# versterker_L.net
KiCad netlist of a schematic drawn in Altium Designer
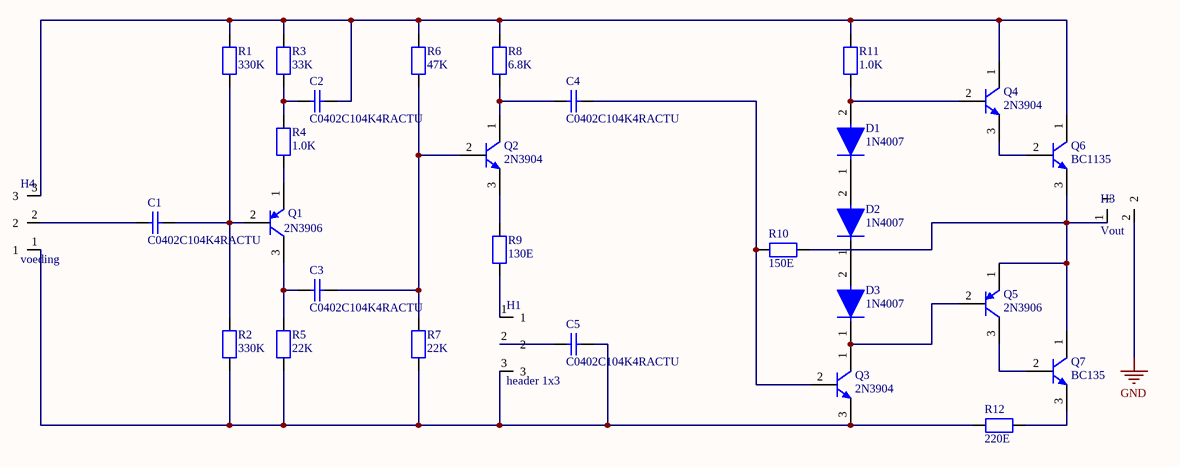
[diagram p0: versterker_L.SchDoc]

(export (version "E")
  (design (tool "Eeschema 10.0.6"))
  (components
    (comp (ref "C1")
      (value "C0402C104K4RACTU")
      (footprint "capacitor SMD")
      (fields (field (name "MANUFACTURER") "Kemet"))
      (libsource (lib "basisSchematicLibrary") (part "capacitor smd"))
    )
    (comp (ref "C2")
      (value "C0402C104K4RACTU")
      (footprint "capacitor SMD")
      (fields (field (name "MANUFACTURER") "Kemet"))
      (libsource (lib "basisSchematicLibrary") (part "capacitor smd"))
    )
    (comp (ref "C3")
      (value "C0402C104K4RACTU")
      (footprint "capacitor SMD")
      (fields (field (name "MANUFACTURER") "Kemet"))
      (libsource (lib "basisSchematicLibrary") (part "capacitor smd"))
    )
    (comp (ref "C4")
      (value "C0402C104K4RACTU")
      (footprint "capacitor SMD")
      (fields (field (name "MANUFACTURER") "Kemet"))
      (libsource (lib "basisSchematicLibrary") (part "capacitor smd"))
    )
    (comp (ref "C5")
      (value "C0402C104K4RACTU")
      (footprint "capacitor SMD")
      (fields (field (name "MANUFACTURER") "Kemet"))
      (libsource (lib "basisSchematicLibrary") (part "capacitor smd"))
    )
    (comp (ref "D1")
      (value "1N4007")
      (footprint "diode")
      (description "Rectifier diode 1000 V 1 A DO-41, ,")
      (fields
        (field (name "MANUFACTURER") "Diotec")
        (field (name "OCTOPART") "https://octopart.com/1n4007-diotec-4040411")
      )
      (libsource (lib "basisSchematicLibrary") (part "diode"))
    )
    (comp (ref "D2")
      (value "1N4007")
      (footprint "diode")
      (description "Rectifier diode 1000 V 1 A DO-41, ,")
      (fields
        (field (name "MANUFACTURER") "Diotec")
        (field (name "OCTOPART") "https://octopart.com/1n4007-diotec-4040411")
      )
      (libsource (lib "basisSchematicLibrary") (part "diode"))
    )
    (comp (ref "D3")
      (value "1N4007")
      (footprint "diode")
      (description "Rectifier diode 1000 V 1 A DO-41, ,")
      (fields
        (field (name "MANUFACTURER") "Diotec")
        (field (name "OCTOPART") "https://octopart.com/1n4007-diotec-4040411")
      )
      (libsource (lib "basisSchematicLibrary") (part "diode"))
    )
    (comp (ref "H1")
      (value "header 1x3")
      (footprint "header 1x3")
      (libsource (lib "headerSchematicLibrary") (part "header 1x3"))
    )
    (comp (ref "H3")
      (value "Vout")
      (footprint "header 1x2")
      (libsource (lib "headerSchematicLibrary") (part "header 1x2"))
    )
    (comp (ref "H4")
      (value "voeding")
      (footprint "header 1x3")
      (libsource (lib "headerSchematicLibrary") (part "header 1x3"))
    )
    (comp (ref "Q1")
      (value "2N3906")
      (footprint "transistor")
      (description "Amplifier Transistor, NPN Silicon, 3-Pin TO-92, Bulk Box")
      (fields (field (name "MANUFACTURER") "On Semiconductor") (field (name "PARTNUMBER") "BC547B"))
      (libsource (lib "basisSchematicLibrary") (part "pnp transistor"))
    )
    (comp (ref "Q2")
      (value "2N3904")
      (footprint "transistor")
      (description "Amplifier Transistor, NPN Silicon, 3-Pin TO-92, Bulk Box")
      (fields (field (name "MANUFACTURER") "On Semiconductor") (field (name "PARTNUMBER") "BC547B"))
      (libsource (lib "basisSchematicLibrary") (part "npn transistor"))
    )
    (comp (ref "Q3")
      (value "2N3904")
      (footprint "transistor")
      (description "Amplifier Transistor, NPN Silicon, 3-Pin TO-92, Bulk Box")
      (fields (field (name "MANUFACTURER") "On Semiconductor") (field (name "PARTNUMBER") "BC547B"))
      (libsource (lib "basisSchematicLibrary") (part "npn transistor"))
    )
    (comp (ref "Q4")
      (value "2N3904")
      (footprint "transistor")
      (description "Amplifier Transistor, NPN Silicon, 3-Pin TO-92, Bulk Box")
      (fields (field (name "MANUFACTURER") "On Semiconductor") (field (name "PARTNUMBER") "BC547B"))
      (libsource (lib "basisSchematicLibrary") (part "npn transistor"))
    )
    (comp (ref "Q5")
      (value "2N3906")
      (footprint "transistor")
      (description "Amplifier Transistor, NPN Silicon, 3-Pin TO-92, Bulk Box")
      (fields (field (name "MANUFACTURER") "On Semiconductor") (field (name "PARTNUMBER") "BC547B"))
      (libsource (lib "basisSchematicLibrary") (part "pnp transistor"))
    )
    (comp (ref "Q6")
      (value "BC1135")
      (footprint "transistor")
      (description "Amplifier Transistor, NPN Silicon, 3-Pin TO-92, Bulk Box")
      (fields (field (name "MANUFACTURER") "On Semiconductor") (field (name "PARTNUMBER") "BC547B"))
      (libsource (lib "basisSchematicLibrary") (part "npn transistor"))
    )
    (comp (ref "Q7")
      (value "BC135")
      (footprint "transistor")
      (description "Amplifier Transistor, NPN Silicon, 3-Pin TO-92, Bulk Box")
      (fields (field (name "MANUFACTURER") "On Semiconductor") (field (name "PARTNUMBER") "BC547B"))
      (libsource (lib "basisSchematicLibrary") (part "npn transistor"))
    )
    (comp (ref "R1")
      (value "330K")
      (footprint "resistor smd")
      (fields (field (name "MANUFACTURER") "Vishay Dale") (field (name "PART NUMBER") "CRCW08050000Z0EA"))
      (libsource (lib "basisSchematicLibrary") (part "resistor smd"))
    )
    (comp (ref "R2")
      (value "330K")
      (footprint "resistor smd")
      (fields (field (name "MANUFACTURER") "Vishay Dale") (field (name "PART NUMBER") "CRCW08050000Z0EA"))
      (libsource (lib "basisSchematicLibrary") (part "resistor smd"))
    )
    (comp (ref "R3")
      (value "33K")
      (footprint "resistor smd")
      (fields (field (name "MANUFACTURER") "Vishay Dale") (field (name "PART NUMBER") "CRCW08050000Z0EA"))
      (libsource (lib "basisSchematicLibrary") (part "resistor smd"))
    )
    (comp (ref "R4")
      (value "1.0K")
      (footprint "resistor smd")
      (fields (field (name "MANUFACTURER") "Vishay Dale") (field (name "PART NUMBER") "CRCW08050000Z0EA"))
      (libsource (lib "basisSchematicLibrary") (part "resistor smd"))
    )
    (comp (ref "R5")
      (value "22K")
      (footprint "resistor smd")
      (fields (field (name "MANUFACTURER") "Vishay Dale") (field (name "PART NUMBER") "CRCW08050000Z0EA"))
      (libsource (lib "basisSchematicLibrary") (part "resistor smd"))
    )
    (comp (ref "R6")
      (value "47K")
      (footprint "resistor smd")
      (fields (field (name "MANUFACTURER") "Vishay Dale") (field (name "PART NUMBER") "CRCW08050000Z0EA"))
      (libsource (lib "basisSchematicLibrary") (part "resistor smd"))
    )
    (comp (ref "R7")
      (value "22K")
      (footprint "resistor smd")
      (fields (field (name "MANUFACTURER") "Vishay Dale") (field (name "PART NUMBER") "CRCW08050000Z0EA"))
      (libsource (lib "basisSchematicLibrary") (part "resistor smd"))
    )
    (comp (ref "R8")
      (value "6.8K")
      (footprint "resistor smd")
      (fields (field (name "MANUFACTURER") "Vishay Dale") (field (name "PART NUMBER") "CRCW08050000Z0EA"))
      (libsource (lib "basisSchematicLibrary") (part "resistor smd"))
    )
    (comp (ref "R9")
      (value "130E")
      (footprint "resistor smd")
      (fields (field (name "MANUFACTURER") "Vishay Dale") (field (name "PART NUMBER") "CRCW08050000Z0EA"))
      (libsource (lib "basisSchematicLibrary") (part "resistor smd"))
    )
    (comp (ref "R10")
      (value "150E")
      (footprint "resistor smd")
      (fields (field (name "MANUFACTURER") "Vishay Dale") (field (name "PART NUMBER") "CRCW08050000Z0EA"))
      (libsource (lib "basisSchematicLibrary") (part "resistor smd"))
    )
    (comp (ref "R11")
      (value "1.0K")
      (footprint "resistor smd")
      (fields (field (name "MANUFACTURER") "Vishay Dale") (field (name "PART NUMBER") "CRCW08050000Z0EA"))
      (libsource (lib "basisSchematicLibrary") (part "resistor smd"))
    )
    (comp (ref "R12")
      (value "220E")
      (footprint "resistor smd")
      (fields (field (name "MANUFACTURER") "Vishay Dale") (field (name "PART NUMBER") "CRCW08050000Z0EA"))
      (libsource (lib "basisSchematicLibrary") (part "resistor smd"))
    )
  )
  (nets
    (net (code "1") (name "GND") (class "Default")
      (node (ref "H3") (pin "2") (pinfunction "2_2") (pintype "passive"))
    )
    (net (code "2") (name "Net-(C1-Pad1)") (class "Default")
      (node (ref "C1") (pin "1") (pinfunction "1_1") (pintype "passive"))
      (node (ref "H4") (pin "2") (pinfunction "2_2") (pintype "passive"))
    )
    (net (code "3") (name "Net-(C2-Pad1)") (class "Default")
      (node (ref "C2") (pin "1") (pinfunction "1_1") (pintype "passive"))
      (node (ref "R3") (pin "1") (pinfunction "1_1") (pintype "passive"))
      (node (ref "R4") (pin "2") (pinfunction "2_2") (pintype "passive"))
    )
    (net (code "4") (name "Net-(C5-Pad1)") (class "Default")
      (node (ref "C5") (pin "1") (pinfunction "1_1") (pintype "passive"))
      (node (ref "H1") (pin "2") (pinfunction "2_2") (pintype "passive"))
    )
    (net (code "5") (name "Net-(D1-A)") (class "Default")
      (node (ref "D1") (pin "2") (pinfunction "A_2") (pintype "passive"))
      (node (ref "Q4") (pin "2") (pinfunction "B_2") (pintype "passive"))
      (node (ref "R11") (pin "1") (pinfunction "1_1") (pintype "passive"))
    )
    (net (code "6") (name "Net-(D1-C)") (class "Default")
      (node (ref "D1") (pin "1") (pinfunction "C_1") (pintype "passive"))
      (node (ref "D2") (pin "2") (pinfunction "A_2") (pintype "passive"))
    )
    (net (code "7") (name "Net-(D2-C)") (class "Default")
      (node (ref "D2") (pin "1") (pinfunction "C_1") (pintype "passive"))
      (node (ref "D3") (pin "2") (pinfunction "A_2") (pintype "passive"))
    )
    (net (code "8") (name "Net-(D3-C)") (class "Default")
      (node (ref "D3") (pin "1") (pinfunction "C_1") (pintype "passive"))
      (node (ref "Q3") (pin "1") (pinfunction "C_1") (pintype "passive"))
      (node (ref "Q5") (pin "2") (pinfunction "B_2") (pintype "passive"))
    )
    (net (code "9") (name "Net-(H1-Pad1)") (class "Default")
      (node (ref "H1") (pin "1") (pinfunction "1_1") (pintype "passive"))
      (node (ref "R9") (pin "1") (pinfunction "1_1") (pintype "passive"))
    )
    (net (code "10") (name "Net-(Q1-B)") (class "Default")
      (node (ref "C1") (pin "2") (pinfunction "2_2") (pintype "passive"))
      (node (ref "Q1") (pin "2") (pinfunction "B_2") (pintype "passive"))
      (node (ref "R1") (pin "1") (pinfunction "1_1") (pintype "passive"))
      (node (ref "R2") (pin "2") (pinfunction "2_2") (pintype "passive"))
    )
    (net (code "11") (name "Net-(Q1-C)") (class "Default")
      (node (ref "Q1") (pin "1") (pinfunction "C_1") (pintype "passive"))
      (node (ref "R4") (pin "1") (pinfunction "1_1") (pintype "passive"))
    )
    (net (code "12") (name "Net-(Q1-E)") (class "Default")
      (node (ref "C3") (pin "1") (pinfunction "1_1") (pintype "passive"))
      (node (ref "Q1") (pin "3") (pinfunction "E_3") (pintype "passive"))
      (node (ref "R5") (pin "2") (pinfunction "2_2") (pintype "passive"))
    )
    (net (code "13") (name "Net-(Q2-B)") (class "Default")
      (node (ref "C3") (pin "2") (pinfunction "2_2") (pintype "passive"))
      (node (ref "Q2") (pin "2") (pinfunction "B_2") (pintype "passive"))
      (node (ref "R6") (pin "1") (pinfunction "1_1") (pintype "passive"))
      (node (ref "R7") (pin "2") (pinfunction "2_2") (pintype "passive"))
    )
    (net (code "14") (name "Net-(Q2-C)") (class "Default")
      (node (ref "C4") (pin "1") (pinfunction "1_1") (pintype "passive"))
      (node (ref "Q2") (pin "1") (pinfunction "C_1") (pintype "passive"))
      (node (ref "R8") (pin "1") (pinfunction "1_1") (pintype "passive"))
    )
    (net (code "15") (name "Net-(Q2-E)") (class "Default")
      (node (ref "Q2") (pin "3") (pinfunction "E_3") (pintype "passive"))
      (node (ref "R9") (pin "2") (pinfunction "2_2") (pintype "passive"))
    )
    (net (code "16") (name "Net-(Q3-B)") (class "Default")
      (node (ref "C4") (pin "2") (pinfunction "2_2") (pintype "passive"))
      (node (ref "Q3") (pin "2") (pinfunction "B_2") (pintype "passive"))
      (node (ref "R10") (pin "1") (pinfunction "1_1") (pintype "passive"))
    )
    (net (code "17") (name "Net-(Q3-E)") (class "Default")
      (node (ref "C5") (pin "2") (pinfunction "2_2") (pintype "passive"))
      (node (ref "H1") (pin "3") (pinfunction "3_3") (pintype "passive"))
      (node (ref "H4") (pin "1") (pinfunction "1_1") (pintype "passive"))
      (node (ref "Q3") (pin "3") (pinfunction "E_3") (pintype "passive"))
      (node (ref "R12") (pin "1") (pinfunction "1_1") (pintype "passive"))
      (node (ref "R2") (pin "1") (pinfunction "1_1") (pintype "passive"))
      (node (ref "R5") (pin "1") (pinfunction "1_1") (pintype "passive"))
      (node (ref "R7") (pin "1") (pinfunction "1_1") (pintype "passive"))
    )
    (net (code "18") (name "Net-(Q4-C)") (class "Default")
      (node (ref "C2") (pin "2") (pinfunction "2_2") (pintype "passive"))
      (node (ref "H4") (pin "3") (pinfunction "3_3") (pintype "passive"))
      (node (ref "Q4") (pin "1") (pinfunction "C_1") (pintype "passive"))
      (node (ref "Q6") (pin "1") (pinfunction "C_1") (pintype "passive"))
      (node (ref "R1") (pin "2") (pinfunction "2_2") (pintype "passive"))
      (node (ref "R11") (pin "2") (pinfunction "2_2") (pintype "passive"))
      (node (ref "R3") (pin "2") (pinfunction "2_2") (pintype "passive"))
      (node (ref "R6") (pin "2") (pinfunction "2_2") (pintype "passive"))
      (node (ref "R8") (pin "2") (pinfunction "2_2") (pintype "passive"))
    )
    (net (code "19") (name "Net-(Q4-E)") (class "Default")
      (node (ref "Q4") (pin "3") (pinfunction "E_3") (pintype "passive"))
      (node (ref "Q6") (pin "2") (pinfunction "B_2") (pintype "passive"))
    )
    (net (code "20") (name "Net-(Q5-C)") (class "Default")
      (node (ref "H3") (pin "1") (pinfunction "1_1") (pintype "passive"))
      (node (ref "Q5") (pin "1") (pinfunction "C_1") (pintype "passive"))
      (node (ref "Q6") (pin "3") (pinfunction "E_3") (pintype "passive"))
      (node (ref "Q7") (pin "1") (pinfunction "C_1") (pintype "passive"))
      (node (ref "R10") (pin "2") (pinfunction "2_2") (pintype "passive"))
    )
    (net (code "21") (name "Net-(Q5-E)") (class "Default")
      (node (ref "Q5") (pin "3") (pinfunction "E_3") (pintype "passive"))
      (node (ref "Q7") (pin "2") (pinfunction "B_2") (pintype "passive"))
    )
    (net (code "22") (name "Net-(Q7-E)") (class "Default")
      (node (ref "Q7") (pin "3") (pinfunction "E_3") (pintype "passive"))
      (node (ref "R12") (pin "2") (pinfunction "2_2") (pintype "passive"))
    )
  )
)
